# audio_spectrum.net
KiCad netlist of a schematic drawn in EAGLE
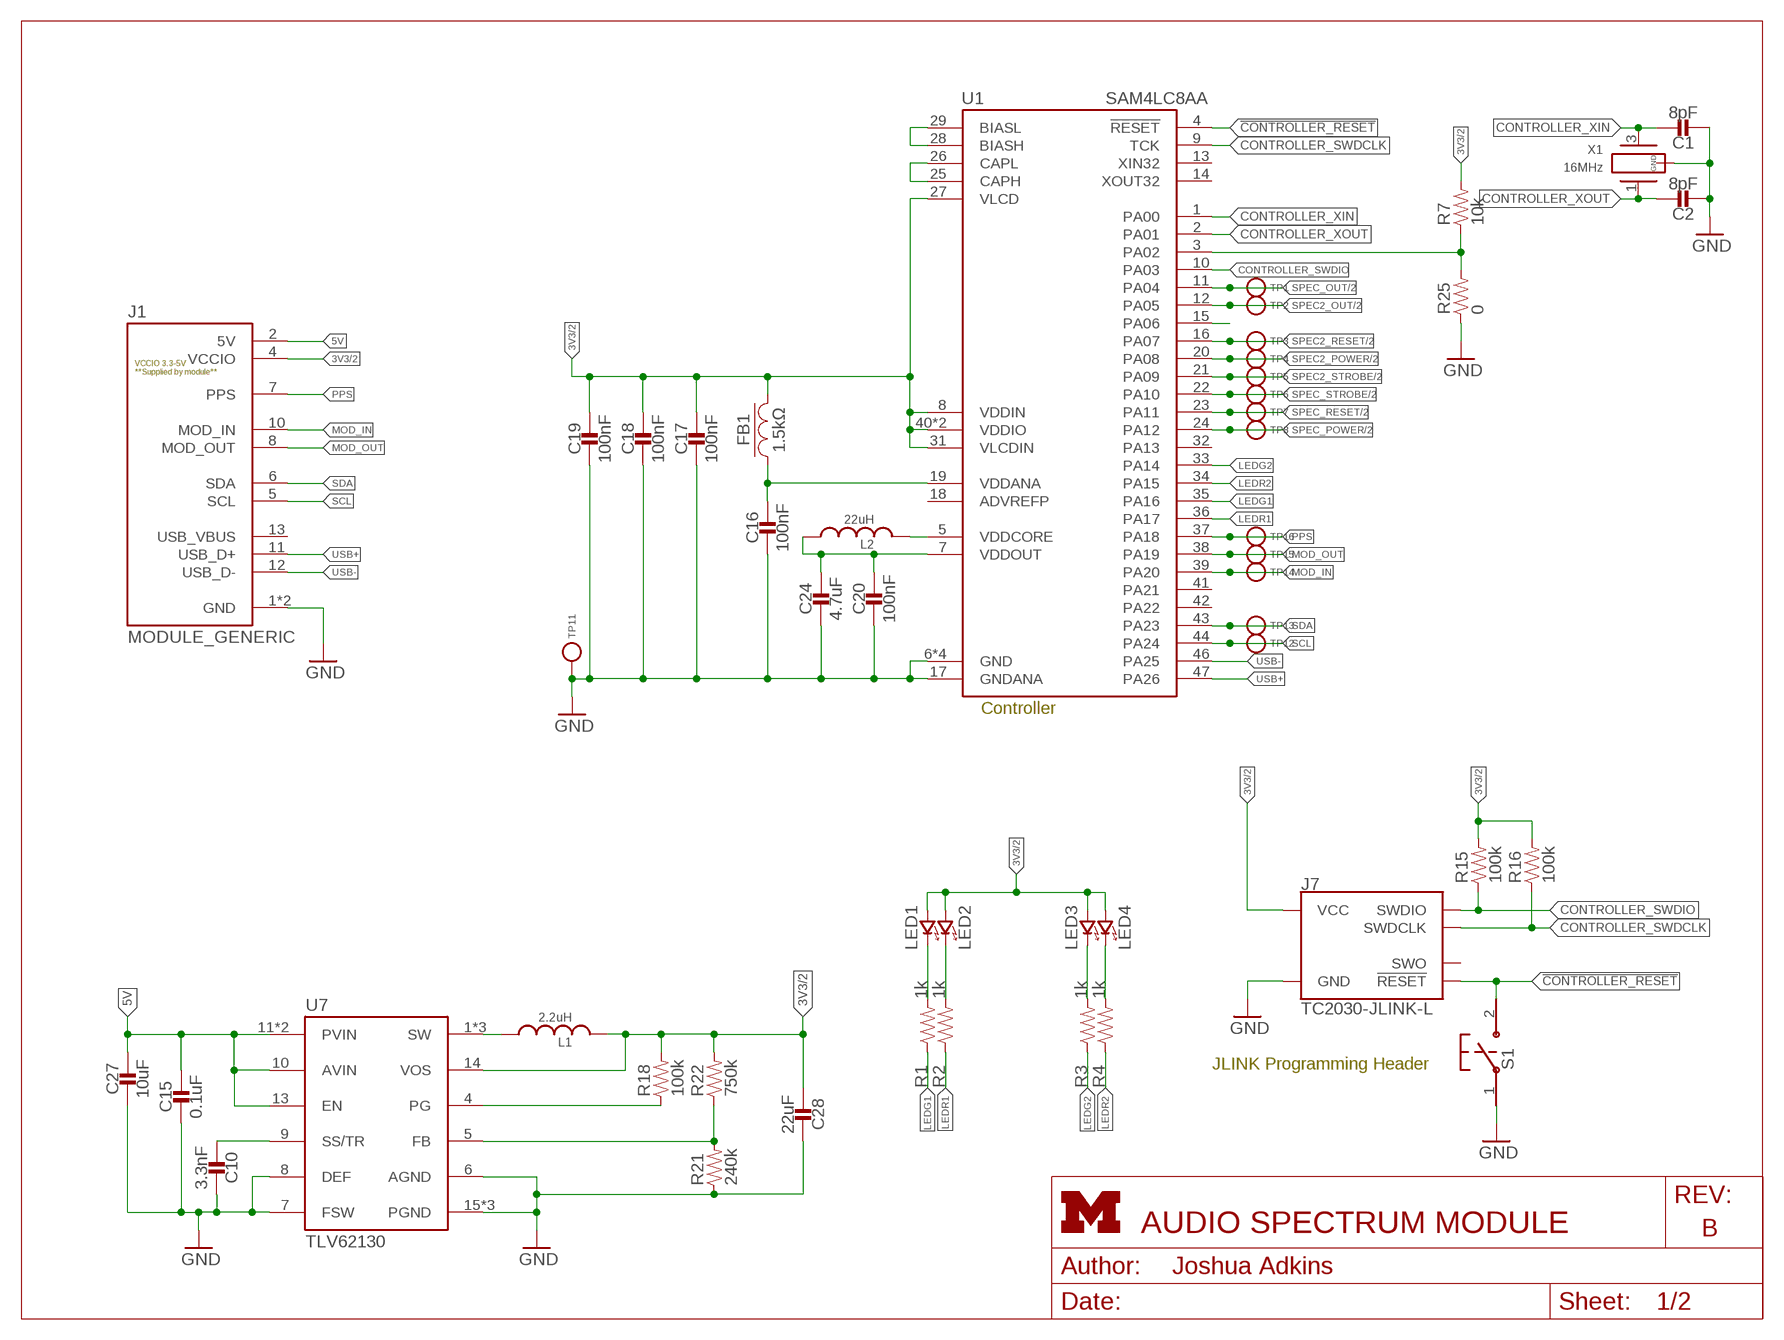
[diagram p0: schematic, sheet 1]
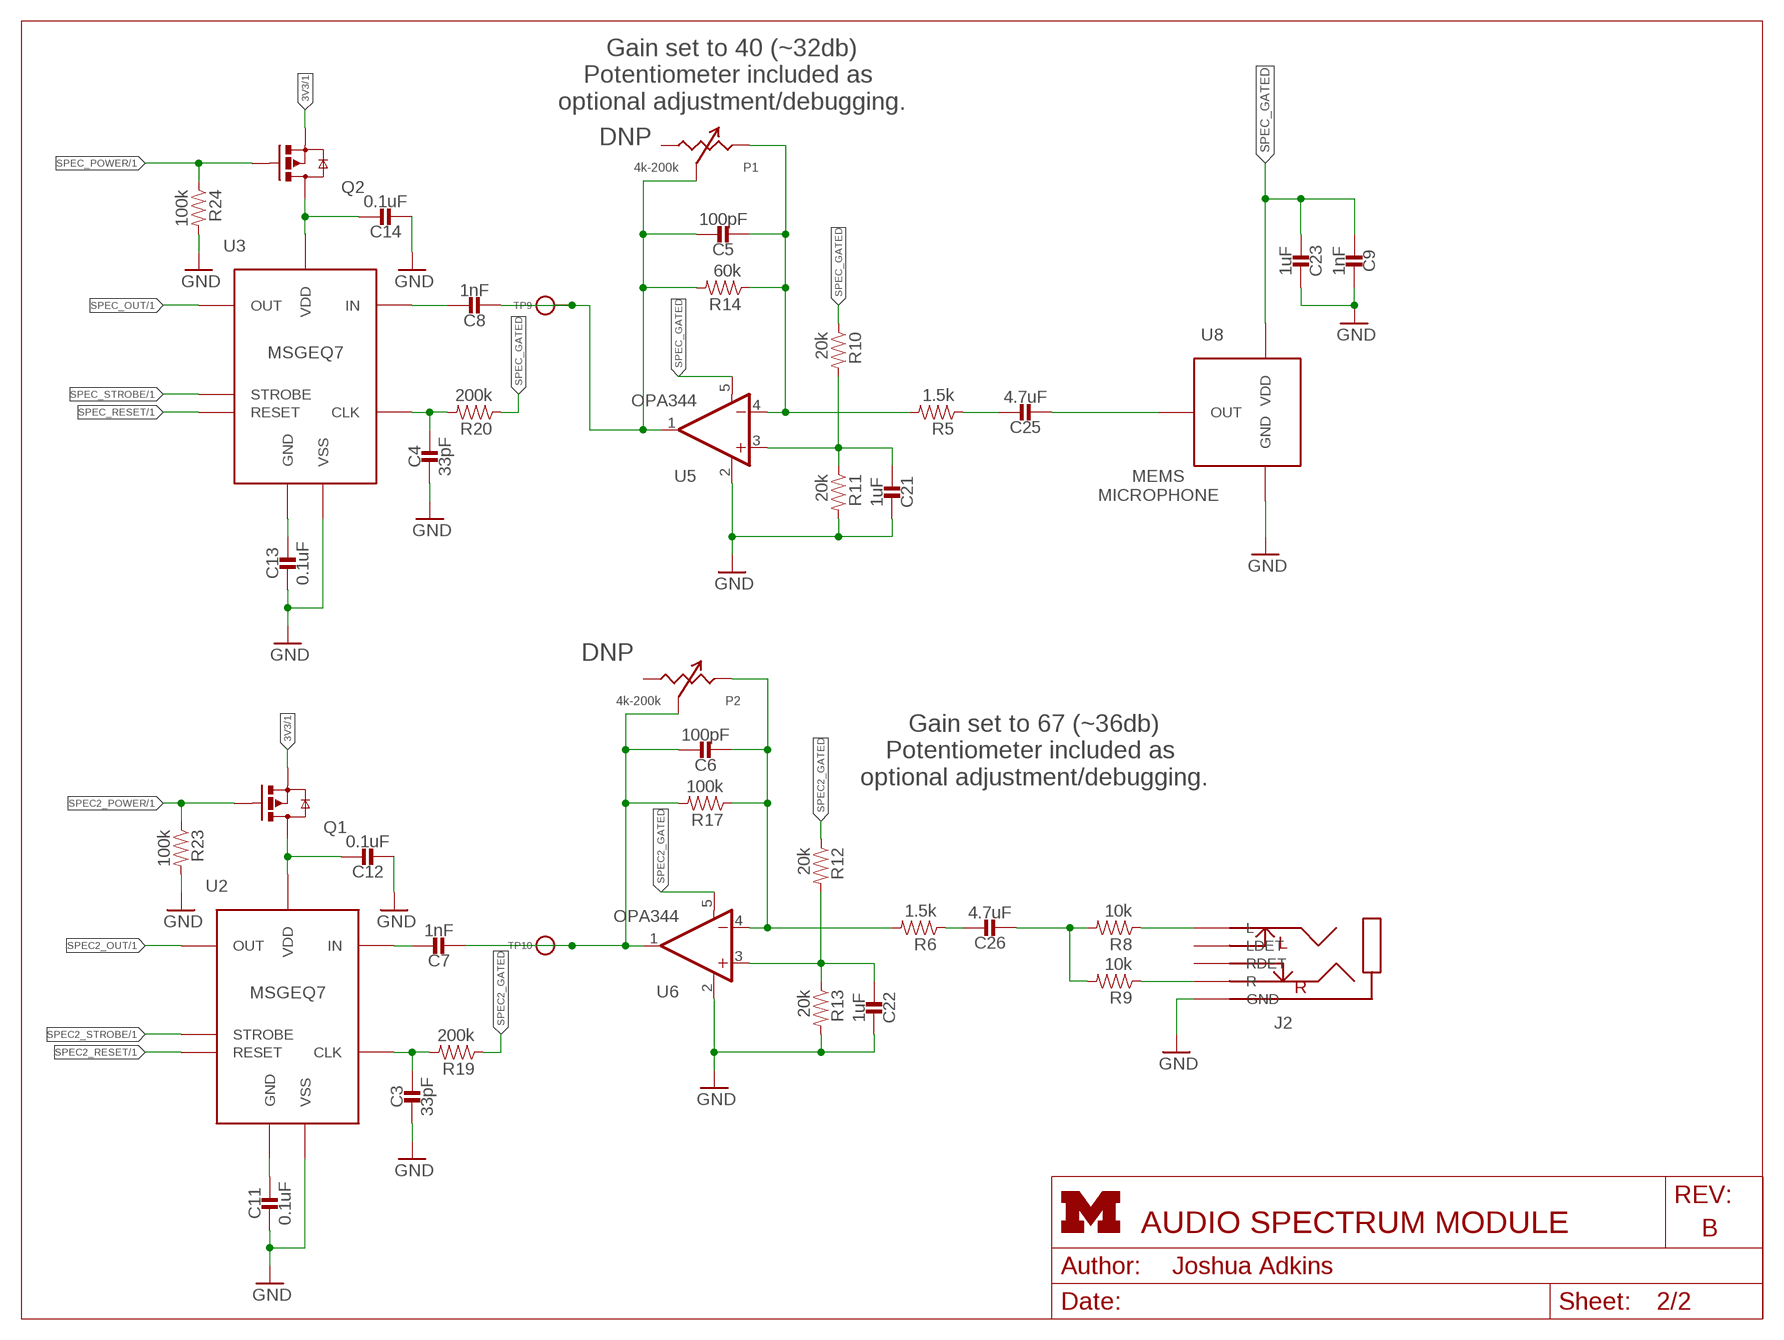
[diagram p1: schematic, sheet 2]

(export (version "E")
  (design (tool "Eeschema 10.0.6"))
  (components
    (comp (ref "C1")
      (value "8pF")
      (footprint "eagle-import:0603_CAP")
      (libsource (lib "eagle-import") (part "CAPACITOR0603_CAP"))
    )
    (comp (ref "C2")
      (value "8pF")
      (footprint "eagle-import:0603_CAP")
      (libsource (lib "eagle-import") (part "CAPACITOR0603_CAP"))
    )
    (comp (ref "C10")
      (value "3.3nF")
      (footprint "eagle-import:0603_CAP")
      (libsource (lib "eagle-import") (part "CAPACITOR0603_CAP"))
    )
    (comp (ref "C15")
      (value "0.1uF")
      (footprint "eagle-import:0603_CAP")
      (libsource (lib "eagle-import") (part "CAPACITOR0603_CAP"))
    )
    (comp (ref "C16")
      (value "100nF")
      (footprint "eagle-import:0603_CAP")
      (libsource (lib "eagle-import") (part "CAPACITOR0603_CAP"))
    )
    (comp (ref "C17")
      (value "100nF")
      (footprint "eagle-import:0603_CAP")
      (libsource (lib "eagle-import") (part "CAPACITOR0603_CAP"))
    )
    (comp (ref "C18")
      (value "100nF")
      (footprint "eagle-import:0603_CAP")
      (libsource (lib "eagle-import") (part "CAPACITOR0603_CAP"))
    )
    (comp (ref "C19")
      (value "100nF")
      (footprint "eagle-import:0603_CAP")
      (libsource (lib "eagle-import") (part "CAPACITOR0603_CAP"))
    )
    (comp (ref "C20")
      (value "100nF")
      (footprint "eagle-import:0402_CAP")
      (libsource (lib "eagle-import") (part "CAPACITOR0402_CAP"))
    )
    (comp (ref "C24")
      (value "4.7uF")
      (footprint "eagle-import:0402_CAP")
      (libsource (lib "eagle-import") (part "CAPACITOR0402_CAP"))
    )
    (comp (ref "C27")
      (value "10uF")
      (footprint "eagle-import:0603_CAP")
      (libsource (lib "eagle-import") (part "CAPACITOR0603_CAP"))
    )
    (comp (ref "C28")
      (value "22uF")
      (footprint "eagle-import:0603_CAP")
      (libsource (lib "eagle-import") (part "CAPACITOR0603_CAP"))
    )
    (comp (ref "FB1")
      (value "1.5kΩ")
      (footprint "eagle-import:0603_CAP")
      (libsource (lib "eagle-import") (part "FERRITE_BEAD0603"))
    )
    (comp (ref "J1")
      (value "MODULE_GENERIC")
      (footprint "eagle-import:MODULE_GENERIC")
      (libsource (lib "eagle-import") (part "MODULE_GENERIC"))
    )
    (comp (ref "J7")
      (value "TC2030-JLINK-L")
      (footprint "eagle-import:TC2030-IDC")
      (libsource (lib "eagle-import") (part "TC2030-JLINK-L"))
    )
    (comp (ref "L1")
      (value "2.2uH")
      (footprint "eagle-import:IHL-1212BZ-11")
      (libsource (lib "eagle-import") (part "INDUCTORIHL"))
    )
    (comp (ref "L2")
      (value "22uH")
      (footprint "eagle-import:1212")
      (libsource (lib "eagle-import") (part "LHQ3NP"))
    )
    (comp (ref "LED1")
      (value "LED0603")
      (footprint "eagle-import:LED-0603")
      (libsource (lib "eagle-import") (part "LED0603"))
    )
    (comp (ref "LED2")
      (value "LED0603")
      (footprint "eagle-import:LED-0603")
      (libsource (lib "eagle-import") (part "LED0603"))
    )
    (comp (ref "LED3")
      (value "LED0603")
      (footprint "eagle-import:LED-0603")
      (libsource (lib "eagle-import") (part "LED0603"))
    )
    (comp (ref "LED4")
      (value "LED0603")
      (footprint "eagle-import:LED-0603")
      (libsource (lib "eagle-import") (part "LED0603"))
    )
    (comp (ref "R1")
      (value "1k")
      (footprint "eagle-import:0603-RES")
      (libsource (lib "eagle-import") (part "RESISTOR0603_RES"))
    )
    (comp (ref "R2")
      (value "1k")
      (footprint "eagle-import:0603-RES")
      (libsource (lib "eagle-import") (part "RESISTOR0603_RES"))
    )
    (comp (ref "R3")
      (value "1k")
      (footprint "eagle-import:0603-RES")
      (libsource (lib "eagle-import") (part "RESISTOR0603_RES"))
    )
    (comp (ref "R4")
      (value "1k")
      (footprint "eagle-import:0603-RES")
      (libsource (lib "eagle-import") (part "RESISTOR0603_RES"))
    )
    (comp (ref "R7")
      (value "10k")
      (footprint "eagle-import:0603-RES")
      (libsource (lib "eagle-import") (part "RESISTOR0603_RES"))
    )
    (comp (ref "R15")
      (value "100k")
      (footprint "eagle-import:0603-RES")
      (libsource (lib "eagle-import") (part "RESISTOR0603_RES"))
    )
    (comp (ref "R16")
      (value "100k")
      (footprint "eagle-import:0603-RES")
      (libsource (lib "eagle-import") (part "RESISTOR0603_RES"))
    )
    (comp (ref "R18")
      (value "100k")
      (footprint "eagle-import:0603-RES")
      (libsource (lib "eagle-import") (part "RESISTOR0603_RES"))
    )
    (comp (ref "R21")
      (value "240k")
      (footprint "eagle-import:0603-RES")
      (libsource (lib "eagle-import") (part "RESISTOR0603_RES"))
    )
    (comp (ref "R22")
      (value "750k")
      (footprint "eagle-import:0603-RES")
      (libsource (lib "eagle-import") (part "RESISTOR0603_RES"))
    )
    (comp (ref "R25")
      (value "0")
      (footprint "eagle-import:0603-RES")
      (libsource (lib "eagle-import") (part "RESISTOR0603_RES"))
    )
    (comp (ref "S1")
      (value "B3U-1000P")
      (footprint "eagle-import:B3U-1000P")
      (libsource (lib "eagle-import") (part "B3U-1000P"))
    )
    (comp (ref "TP1")
      (value "TEST_POINT_0.040IN")
      (footprint "eagle-import:TESTPOINT_0.040IN")
      (libsource (lib "eagle-import") (part "TEST_POINT_0.040IN"))
    )
    (comp (ref "TP2")
      (value "TEST_POINT_0.040IN")
      (footprint "eagle-import:TESTPOINT_0.040IN")
      (libsource (lib "eagle-import") (part "TEST_POINT_0.040IN"))
    )
    (comp (ref "TP3")
      (value "TEST_POINT_0.040IN")
      (footprint "eagle-import:TESTPOINT_0.040IN")
      (libsource (lib "eagle-import") (part "TEST_POINT_0.040IN"))
    )
    (comp (ref "TP4")
      (value "TEST_POINT_0.040IN")
      (footprint "eagle-import:TESTPOINT_0.040IN")
      (libsource (lib "eagle-import") (part "TEST_POINT_0.040IN"))
    )
    (comp (ref "TP5")
      (value "TEST_POINT_0.040IN")
      (footprint "eagle-import:TESTPOINT_0.040IN")
      (libsource (lib "eagle-import") (part "TEST_POINT_0.040IN"))
    )
    (comp (ref "TP6")
      (value "TEST_POINT_0.040IN")
      (footprint "eagle-import:TESTPOINT_0.040IN")
      (libsource (lib "eagle-import") (part "TEST_POINT_0.040IN"))
    )
    (comp (ref "TP7")
      (value "TEST_POINT_0.040IN")
      (footprint "eagle-import:TESTPOINT_0.040IN")
      (libsource (lib "eagle-import") (part "TEST_POINT_0.040IN"))
    )
    (comp (ref "TP8")
      (value "TEST_POINT_0.040IN")
      (footprint "eagle-import:TESTPOINT_0.040IN")
      (libsource (lib "eagle-import") (part "TEST_POINT_0.040IN"))
    )
    (comp (ref "TP11")
      (value "TEST_POINT_0.040IN")
      (footprint "eagle-import:TESTPOINT_0.040IN")
      (libsource (lib "eagle-import") (part "TEST_POINT_0.040IN"))
    )
    (comp (ref "TP12")
      (value "TEST_POINT_0.040IN")
      (footprint "eagle-import:TESTPOINT_0.040IN")
      (libsource (lib "eagle-import") (part "TEST_POINT_0.040IN"))
    )
    (comp (ref "TP13")
      (value "TEST_POINT_0.040IN")
      (footprint "eagle-import:TESTPOINT_0.040IN")
      (libsource (lib "eagle-import") (part "TEST_POINT_0.040IN"))
    )
    (comp (ref "TP14")
      (value "TEST_POINT_0.040IN")
      (footprint "eagle-import:TESTPOINT_0.040IN")
      (libsource (lib "eagle-import") (part "TEST_POINT_0.040IN"))
    )
    (comp (ref "TP15")
      (value "TEST_POINT_0.040IN")
      (footprint "eagle-import:TESTPOINT_0.040IN")
      (libsource (lib "eagle-import") (part "TEST_POINT_0.040IN"))
    )
    (comp (ref "TP16")
      (value "TEST_POINT_0.040IN")
      (footprint "eagle-import:TESTPOINT_0.040IN")
      (libsource (lib "eagle-import") (part "TEST_POINT_0.040IN"))
    )
    (comp (ref "U1")
      (value "SAM4LC8AA")
      (footprint "eagle-import:QFN-48-7MM")
      (libsource (lib "eagle-import") (part "SAM4LC8AA"))
    )
    (comp (ref "U7")
      (value "TLV62130")
      (footprint "eagle-import:TQFN-16_3MM")
      (libsource (lib "eagle-import") (part "TLV62130"))
    )
    (comp (ref "X1")
      (value "16MHz")
      (footprint "eagle-import:FHXXX")
      (libsource (lib "eagle-import") (part "FH1600015"))
    )
    (comp (ref "C3")
      (value "33pF")
      (footprint "eagle-import:0603_CAP")
      (libsource (lib "eagle-import") (part "CAPACITOR0603_CAP"))
    )
    (comp (ref "C4")
      (value "33pF")
      (footprint "eagle-import:0603_CAP")
      (libsource (lib "eagle-import") (part "CAPACITOR0603_CAP"))
    )
    (comp (ref "C5")
      (value "100pF")
      (footprint "eagle-import:0603_CAP")
      (libsource (lib "eagle-import") (part "CAPACITOR0603_CAP"))
    )
    (comp (ref "C6")
      (value "100pF")
      (footprint "eagle-import:0603_CAP")
      (libsource (lib "eagle-import") (part "CAPACITOR0603_CAP"))
    )
    (comp (ref "C7")
      (value "1nF")
      (footprint "eagle-import:0603_CAP")
      (libsource (lib "eagle-import") (part "CAPACITOR0603_CAP"))
    )
    (comp (ref "C8")
      (value "1nF")
      (footprint "eagle-import:0603_CAP")
      (libsource (lib "eagle-import") (part "CAPACITOR0603_CAP"))
    )
    (comp (ref "C9")
      (value "1nF")
      (footprint "eagle-import:0603_CAP")
      (libsource (lib "eagle-import") (part "CAPACITOR0603_CAP"))
    )
    (comp (ref "C11")
      (value "0.1uF")
      (footprint "eagle-import:0603_CAP")
      (libsource (lib "eagle-import") (part "CAPACITOR0603_CAP"))
    )
    (comp (ref "C12")
      (value "0.1uF")
      (footprint "eagle-import:0603_CAP")
      (libsource (lib "eagle-import") (part "CAPACITOR0603_CAP"))
    )
    (comp (ref "C13")
      (value "0.1uF")
      (footprint "eagle-import:0603_CAP")
      (libsource (lib "eagle-import") (part "CAPACITOR0603_CAP"))
    )
    (comp (ref "C14")
      (value "0.1uF")
      (footprint "eagle-import:0603_CAP")
      (libsource (lib "eagle-import") (part "CAPACITOR0603_CAP"))
    )
    (comp (ref "C21")
      (value "1uF")
      (footprint "eagle-import:0603_CAP")
      (libsource (lib "eagle-import") (part "CAPACITOR0603_CAP"))
    )
    (comp (ref "C22")
      (value "1uF")
      (footprint "eagle-import:0603_CAP")
      (libsource (lib "eagle-import") (part "CAPACITOR0603_CAP"))
    )
    (comp (ref "C23")
      (value "1uF")
      (footprint "eagle-import:0603_CAP")
      (libsource (lib "eagle-import") (part "CAPACITOR0603_CAP"))
    )
    (comp (ref "C25")
      (value "4.7uF")
      (footprint "eagle-import:0603_CAP")
      (libsource (lib "eagle-import") (part "CAPACITOR0603_CAP"))
    )
    (comp (ref "C26")
      (value "4.7uF")
      (footprint "eagle-import:0603_CAP")
      (libsource (lib "eagle-import") (part "CAPACITOR0603_CAP"))
    )
    (comp (ref "J2")
      (value "AUDIO-JACK-VERTICAL")
      (footprint "eagle-import:AUDIO-JACK-VERTICAL")
      (libsource (lib "eagle-import") (part "AUDIO-JACK-VERTICAL"))
    )
    (comp (ref "P1")
      (value "4k-200k")
      (footprint "eagle-import:TC33X-2")
      (libsource (lib "eagle-import") (part "POTTC33X"))
    )
    (comp (ref "P2")
      (value "4k-200k")
      (footprint "eagle-import:TC33X-2")
      (libsource (lib "eagle-import") (part "POTTC33X"))
    )
    (comp (ref "Q1")
      (value "NX3008PBK")
      (footprint "eagle-import:SOT23-3")
      (libsource (lib "eagle-import") (part "NX3008PBK"))
    )
    (comp (ref "Q2")
      (value "NX3008PBK")
      (footprint "eagle-import:SOT23-3")
      (libsource (lib "eagle-import") (part "NX3008PBK"))
    )
    (comp (ref "R5")
      (value "1.5k")
      (footprint "eagle-import:0603-RES")
      (libsource (lib "eagle-import") (part "RESISTOR0603_RES"))
    )
    (comp (ref "R6")
      (value "1.5k")
      (footprint "eagle-import:0603-RES")
      (libsource (lib "eagle-import") (part "RESISTOR0603_RES"))
    )
    (comp (ref "R8")
      (value "10k")
      (footprint "eagle-import:0603-RES")
      (libsource (lib "eagle-import") (part "RESISTOR0603_RES"))
    )
    (comp (ref "R9")
      (value "10k")
      (footprint "eagle-import:0603-RES")
      (libsource (lib "eagle-import") (part "RESISTOR0603_RES"))
    )
    (comp (ref "R10")
      (value "20k")
      (footprint "eagle-import:0603-RES")
      (libsource (lib "eagle-import") (part "RESISTOR0603_RES"))
    )
    (comp (ref "R11")
      (value "20k")
      (footprint "eagle-import:0603-RES")
      (libsource (lib "eagle-import") (part "RESISTOR0603_RES"))
    )
    (comp (ref "R12")
      (value "20k")
      (footprint "eagle-import:0603-RES")
      (libsource (lib "eagle-import") (part "RESISTOR0603_RES"))
    )
    (comp (ref "R13")
      (value "20k")
      (footprint "eagle-import:0603-RES")
      (libsource (lib "eagle-import") (part "RESISTOR0603_RES"))
    )
    (comp (ref "R14")
      (value "60k")
      (footprint "eagle-import:0603-RES")
      (libsource (lib "eagle-import") (part "RESISTOR0603_RES"))
    )
    (comp (ref "R17")
      (value "100k")
      (footprint "eagle-import:0603-RES")
      (libsource (lib "eagle-import") (part "RESISTOR0603_RES"))
    )
    (comp (ref "R19")
      (value "200k")
      (footprint "eagle-import:0603-RES")
      (libsource (lib "eagle-import") (part "RESISTOR0603_RES"))
    )
    (comp (ref "R20")
      (value "200k")
      (footprint "eagle-import:0603-RES")
      (libsource (lib "eagle-import") (part "RESISTOR0603_RES"))
    )
    (comp (ref "R23")
      (value "100k")
      (footprint "eagle-import:0603-RES")
      (libsource (lib "eagle-import") (part "RESISTOR0603_RES"))
    )
    (comp (ref "R24")
      (value "100k")
      (footprint "eagle-import:0603-RES")
      (libsource (lib "eagle-import") (part "RESISTOR0603_RES"))
    )
    (comp (ref "TP9")
      (value "TEST_POINT_0.040IN")
      (footprint "eagle-import:TESTPOINT_0.040IN")
      (libsource (lib "eagle-import") (part "TEST_POINT_0.040IN"))
    )
    (comp (ref "TP10")
      (value "TEST_POINT_0.040IN")
      (footprint "eagle-import:TESTPOINT_0.040IN")
      (libsource (lib "eagle-import") (part "TEST_POINT_0.040IN"))
    )
    (comp (ref "U2")
      (value "MSGEQ7")
      (footprint "eagle-import:DIP-8")
      (libsource (lib "eagle-import") (part "MSGEQ7"))
    )
    (comp (ref "U3")
      (value "MSGEQ7")
      (footprint "eagle-import:DIP-8")
      (libsource (lib "eagle-import") (part "MSGEQ7"))
    )
    (comp (ref "U5")
      (value "OPA344")
      (footprint "eagle-import:SOT23-5")
      (libsource (lib "eagle-import") (part "OPA344"))
    )
    (comp (ref "U6")
      (value "OPA344")
      (footprint "eagle-import:SOT23-5")
      (libsource (lib "eagle-import") (part "OPA344"))
    )
    (comp (ref "U8")
      (value "MP23AB02B")
      (footprint "eagle-import:MP23AB02B")
      (libsource (lib "eagle-import") (part "MP23AB02B"))
    )
  )
  (nets
    (net (code "1") (name "3V3") (class "Default")
      (node (ref "C17") (pin "1") (pinfunction "1_1") (pintype "bidirectional"))
      (node (ref "C18") (pin "1") (pinfunction "1_1") (pintype "bidirectional"))
      (node (ref "C19") (pin "1") (pinfunction "1_1") (pintype "bidirectional"))
      (node (ref "C28") (pin "2") (pinfunction "2_2") (pintype "bidirectional"))
      (node (ref "FB1") (pin "2") (pinfunction "P$2_2") (pintype "bidirectional"))
      (node (ref "J1") (pin "4") (pinfunction "VCCIO_4") (pintype "bidirectional"))
      (node (ref "J7") (pin "1") (pinfunction "VCC_1") (pintype "bidirectional"))
      (node (ref "L1") (pin "P$2") (pinfunction "2_P$2") (pintype "bidirectional"))
      (node (ref "LED1") (pin "A") (pinfunction "ANODE_A") (pintype "bidirectional"))
      (node (ref "LED2") (pin "A") (pinfunction "ANODE_A") (pintype "bidirectional"))
      (node (ref "LED3") (pin "A") (pinfunction "ANODE_A") (pintype "bidirectional"))
      (node (ref "LED4") (pin "A") (pinfunction "ANODE_A") (pintype "bidirectional"))
      (node (ref "Q1") (pin "2") (pinfunction "S_2") (pintype "passive"))
      (node (ref "Q2") (pin "2") (pinfunction "S_2") (pintype "passive"))
      (node (ref "R15") (pin "2") (pinfunction "2_2") (pintype "passive"))
      (node (ref "R16") (pin "2") (pinfunction "2_2") (pintype "passive"))
      (node (ref "R18") (pin "2") (pinfunction "2_2") (pintype "passive"))
      (node (ref "R22") (pin "2") (pinfunction "2_2") (pintype "passive"))
      (node (ref "R7") (pin "2") (pinfunction "2_2") (pintype "passive"))
      (node (ref "U1") (pin "27") (pinfunction "VLCD_27") (pintype "bidirectional"))
      (node (ref "U1") (pin "31") (pinfunction "VLCDIN_31") (pintype "power_in"))
      (node (ref "U1") (pin "40") (pinfunction "VDDIO_40") (pintype "power_in"))
      (node (ref "U1") (pin "45") (pinfunction "VDDIO_45") (pintype "power_in"))
      (node (ref "U1") (pin "8") (pinfunction "VDDIN_8") (pintype "power_in"))
      (node (ref "U7") (pin "14") (pinfunction "VOS_14") (pintype "bidirectional"))
    )
    (net (code "2") (name "5V") (class "Default")
      (node (ref "C15") (pin "1") (pinfunction "1_1") (pintype "bidirectional"))
      (node (ref "C27") (pin "1") (pinfunction "1_1") (pintype "bidirectional"))
      (node (ref "J1") (pin "2") (pinfunction "5V_2") (pintype "bidirectional"))
      (node (ref "U7") (pin "10") (pinfunction "AVIN_10") (pintype "bidirectional"))
      (node (ref "U7") (pin "11") (pinfunction "PVIN_11") (pintype "bidirectional"))
      (node (ref "U7") (pin "12") (pinfunction "PVIN_12") (pintype "bidirectional"))
      (node (ref "U7") (pin "13") (pinfunction "EN_13") (pintype "bidirectional"))
    )
    (net (code "3") (name "CONTROLLER_SWDCLK") (class "Default")
      (node (ref "J7") (pin "4") (pinfunction "SWDCLK_4") (pintype "bidirectional"))
      (node (ref "R16") (pin "1") (pinfunction "1_1") (pintype "passive"))
      (node (ref "U1") (pin "9") (pinfunction "TCK_9") (pintype "bidirectional"))
    )
    (net (code "4") (name "CONTROLLER_SWDIO") (class "Default")
      (node (ref "J7") (pin "2") (pinfunction "SWDIO_2") (pintype "bidirectional"))
      (node (ref "R15") (pin "1") (pinfunction "1_1") (pintype "passive"))
      (node (ref "U1") (pin "10") (pinfunction "PA03_10") (pintype "bidirectional"))
    )
    (net (code "5") (name "CONTROLLER_XIN") (class "Default")
      (node (ref "C1") (pin "1") (pinfunction "1_1") (pintype "bidirectional"))
      (node (ref "U1") (pin "1") (pinfunction "PA00_1") (pintype "bidirectional"))
      (node (ref "X1") (pin "3") (pinfunction "2_3") (pintype "bidirectional"))
    )
    (net (code "6") (name "CONTROLLER_XOUT") (class "Default")
      (node (ref "C2") (pin "1") (pinfunction "1_1") (pintype "bidirectional"))
      (node (ref "U1") (pin "2") (pinfunction "PA01_2") (pintype "bidirectional"))
      (node (ref "X1") (pin "1") (pinfunction "1_1") (pintype "bidirectional"))
    )
    (net (code "7") (name "GND") (class "Default")
      (node (ref "C1") (pin "2") (pinfunction "2_2") (pintype "bidirectional"))
      (node (ref "C10") (pin "1") (pinfunction "1_1") (pintype "bidirectional"))
      (node (ref "C11") (pin "2") (pinfunction "2_2") (pintype "bidirectional"))
      (node (ref "C12") (pin "2") (pinfunction "2_2") (pintype "bidirectional"))
      (node (ref "C13") (pin "2") (pinfunction "2_2") (pintype "bidirectional"))
      (node (ref "C14") (pin "2") (pinfunction "2_2") (pintype "bidirectional"))
      (node (ref "C15") (pin "2") (pinfunction "2_2") (pintype "bidirectional"))
      (node (ref "C16") (pin "2") (pinfunction "2_2") (pintype "bidirectional"))
      (node (ref "C17") (pin "2") (pinfunction "2_2") (pintype "bidirectional"))
      (node (ref "C18") (pin "2") (pinfunction "2_2") (pintype "bidirectional"))
      (node (ref "C19") (pin "2") (pinfunction "2_2") (pintype "bidirectional"))
      (node (ref "C2") (pin "2") (pinfunction "2_2") (pintype "bidirectional"))
      (node (ref "C20") (pin "2") (pinfunction "2_2") (pintype "bidirectional"))
      (node (ref "C21") (pin "1") (pinfunction "1_1") (pintype "bidirectional"))
      (node (ref "C22") (pin "1") (pinfunction "1_1") (pintype "bidirectional"))
      (node (ref "C23") (pin "1") (pinfunction "1_1") (pintype "bidirectional"))
      (node (ref "C24") (pin "2") (pinfunction "2_2") (pintype "bidirectional"))
      (node (ref "C27") (pin "2") (pinfunction "2_2") (pintype "bidirectional"))
      (node (ref "C28") (pin "1") (pinfunction "1_1") (pintype "bidirectional"))
      (node (ref "C3") (pin "2") (pinfunction "2_2") (pintype "bidirectional"))
      (node (ref "C4") (pin "2") (pinfunction "2_2") (pintype "bidirectional"))
      (node (ref "C9") (pin "1") (pinfunction "1_1") (pintype "bidirectional"))
      (node (ref "J1") (pin "1") (pinfunction "GND_1") (pintype "bidirectional"))
      (node (ref "J1") (pin "14") (pinfunction "GND_14") (pintype "bidirectional"))
      (node (ref "J2") (pin "5") (pinfunction "GND_5") (pintype "bidirectional"))
      (node (ref "J7") (pin "5") (pinfunction "GND_5") (pintype "bidirectional"))
      (node (ref "R11") (pin "2") (pinfunction "2_2") (pintype "passive"))
      (node (ref "R13") (pin "2") (pinfunction "2_2") (pintype "passive"))
      (node (ref "R21") (pin "1") (pinfunction "1_1") (pintype "passive"))
      (node (ref "R23") (pin "2") (pinfunction "2_2") (pintype "passive"))
      (node (ref "R24") (pin "2") (pinfunction "2_2") (pintype "passive"))
      (node (ref "R25") (pin "1") (pinfunction "1_1") (pintype "passive"))
      (node (ref "S1") (pin "1") (pinfunction "P$1_1") (pintype "passive"))
      (node (ref "TP11") (pin "TESTPOINT") (pinfunction "TESTPOINT_TESTPOINT") (pintype "bidirectional"))
      (node (ref "U1") (pin "17") (pinfunction "GNDANA_17") (pintype "power_in"))
      (node (ref "U1") (pin "30") (pinfunction "GND_30") (pintype "power_in"))
      (node (ref "U1") (pin "48") (pinfunction "GND_48") (pintype "power_in"))
      (node (ref "U1") (pin "6") (pinfunction "GND_6") (pintype "power_in"))
      (node (ref "U1") (pin "THERMAL") (pinfunction "GND_THERMAL") (pintype "power_in"))
      (node (ref "U2") (pin "2") (pinfunction "VSS_2") (pintype "bidirectional"))
      (node (ref "U3") (pin "2") (pinfunction "VSS_2") (pintype "bidirectional"))
      (node (ref "U5") (pin "2") (pinfunction "V-_2") (pintype "power_in"))
      (node (ref "U6") (pin "2") (pinfunction "V-_2") (pintype "power_in"))
      (node (ref "U7") (pin "15") (pinfunction "PGND_15") (pintype "bidirectional"))
      (node (ref "U7") (pin "16") (pinfunction "PGND_16") (pintype "bidirectional"))
      (node (ref "U7") (pin "6") (pinfunction "AGND_6") (pintype "bidirectional"))
      (node (ref "U7") (pin "7") (pinfunction "FSW_7") (pintype "bidirectional"))
      (node (ref "U7") (pin "8") (pinfunction "DEF_8") (pintype "bidirectional"))
      (node (ref "U7") (pin "GND") (pinfunction "PGND_GND") (pintype "bidirectional"))
      (node (ref "U8") (pin "3") (pinfunction "GND_3") (pintype "bidirectional"))
      (node (ref "X1") (pin "2") (pinfunction "GND_2") (pintype "bidirectional"))
      (node (ref "X1") (pin "4") (pinfunction "GND_4") (pintype "bidirectional"))
    )
    (net (code "8") (name "LEDG1") (class "Default")
      (node (ref "R1") (pin "1") (pinfunction "1_1") (pintype "passive"))
      (node (ref "U1") (pin "35") (pinfunction "PA16_35") (pintype "bidirectional"))
    )
    (net (code "9") (name "LEDG2") (class "Default")
      (node (ref "R3") (pin "1") (pinfunction "1_1") (pintype "passive"))
      (node (ref "U1") (pin "33") (pinfunction "PA14_33") (pintype "bidirectional"))
    )
    (net (code "10") (name "LEDR1") (class "Default")
      (node (ref "R2") (pin "1") (pinfunction "1_1") (pintype "passive"))
      (node (ref "U1") (pin "36") (pinfunction "PA17_36") (pintype "bidirectional"))
    )
    (net (code "11") (name "LEDR2") (class "Default")
      (node (ref "R4") (pin "1") (pinfunction "1_1") (pintype "passive"))
      (node (ref "U1") (pin "34") (pinfunction "PA15_34") (pintype "bidirectional"))
    )
    (net (code "12") (name "MOD_IN") (class "Default")
      (node (ref "J1") (pin "10") (pinfunction "MOD_IN_10") (pintype "bidirectional"))
      (node (ref "TP14") (pin "TESTPOINT") (pinfunction "TESTPOINT_TESTPOINT") (pintype "bidirectional"))
      (node (ref "U1") (pin "39") (pinfunction "PA20_39") (pintype "bidirectional"))
    )
    (net (code "13") (name "MOD_OUT") (class "Default")
      (node (ref "J1") (pin "8") (pinfunction "MOD_OUT_8") (pintype "bidirectional"))
      (node (ref "TP15") (pin "TESTPOINT") (pinfunction "TESTPOINT_TESTPOINT") (pintype "bidirectional"))
      (node (ref "U1") (pin "38") (pinfunction "PA19_38") (pintype "bidirectional"))
    )
    (net (code "14") (name "Net-(C25-Pad1)") (class "Default")
      (node (ref "C25") (pin "1") (pinfunction "1_1") (pintype "bidirectional"))
      (node (ref "R5") (pin "1") (pinfunction "1_1") (pintype "passive"))
    )
    (net (code "15") (name "Net-(C26-Pad1)") (class "Default")
      (node (ref "C26") (pin "1") (pinfunction "1_1") (pintype "bidirectional"))
      (node (ref "R6") (pin "1") (pinfunction "1_1") (pintype "passive"))
    )
    (net (code "16") (name "Net-(C26-Pad2)") (class "Default")
      (node (ref "C26") (pin "2") (pinfunction "2_2") (pintype "bidirectional"))
      (node (ref "R8") (pin "2") (pinfunction "2_2") (pintype "passive"))
      (node (ref "R9") (pin "2") (pinfunction "2_2") (pintype "passive"))
    )
    (net (code "17") (name "Net-(FB1-P$1)") (class "Default")
      (node (ref "C16") (pin "1") (pinfunction "1_1") (pintype "bidirectional"))
      (node (ref "FB1") (pin "1") (pinfunction "P$1_1") (pintype "bidirectional"))
      (node (ref "U1") (pin "19") (pinfunction "VDDANA_19") (pintype "power_in"))
    )
    (net (code "18") (name "Net-(J2-L)") (class "Default")
      (node (ref "J2") (pin "4") (pinfunction "L_4") (pintype "bidirectional"))
      (node (ref "R8") (pin "1") (pinfunction "1_1") (pintype "passive"))
    )
    (net (code "19") (name "Net-(J2-R)") (class "Default")
      (node (ref "J2") (pin "1") (pinfunction "R_1") (pintype "bidirectional"))
      (node (ref "R9") (pin "1") (pinfunction "1_1") (pintype "passive"))
    )
    (net (code "20") (name "Net-(L1-1)") (class "Default")
      (node (ref "L1") (pin "P$1") (pinfunction "1_P$1") (pintype "bidirectional"))
      (node (ref "U7") (pin "1") (pinfunction "SW_1") (pintype "bidirectional"))
      (node (ref "U7") (pin "2") (pinfunction "SW_2") (pintype "bidirectional"))
      (node (ref "U7") (pin "3") (pinfunction "SW_3") (pintype "bidirectional"))
    )
    (net (code "21") (name "Net-(L2-1)") (class "Default")
      (node (ref "C20") (pin "1") (pinfunction "1_1") (pintype "bidirectional"))
      (node (ref "C24") (pin "1") (pinfunction "1_1") (pintype "bidirectional"))
      (node (ref "L2") (pin "P$1") (pinfunction "1_P$1") (pintype "bidirectional"))
      (node (ref "U1") (pin "7") (pinfunction "VDDOUT_7") (pintype "power_in"))
    )
    (net (code "22") (name "Net-(L2-2)") (class "Default")
      (node (ref "L2") (pin "P$2") (pinfunction "2_P$2") (pintype "bidirectional"))
      (node (ref "U1") (pin "5") (pinfunction "VDDCORE_5") (pintype "power_in"))
    )
    (net (code "23") (name "Net-(LED1-CATHODE)") (class "Default")
      (node (ref "LED1") (pin "C") (pinfunction "CATHODE_C") (pintype "bidirectional"))
      (node (ref "R1") (pin "2") (pinfunction "2_2") (pintype "passive"))
    )
    (net (code "24") (name "Net-(LED2-CATHODE)") (class "Default")
      (node (ref "LED2") (pin "C") (pinfunction "CATHODE_C") (pintype "bidirectional"))
      (node (ref "R2") (pin "2") (pinfunction "2_2") (pintype "passive"))
    )
    (net (code "25") (name "Net-(LED3-CATHODE)") (class "Default")
      (node (ref "LED3") (pin "C") (pinfunction "CATHODE_C") (pintype "bidirectional"))
      (node (ref "R3") (pin "2") (pinfunction "2_2") (pintype "passive"))
    )
    (net (code "26") (name "Net-(LED4-CATHODE)") (class "Default")
      (node (ref "LED4") (pin "C") (pinfunction "CATHODE_C") (pintype "bidirectional"))
      (node (ref "R4") (pin "2") (pinfunction "2_2") (pintype "passive"))
    )
    (net (code "27") (name "Net-(P1-CW)") (class "Default")
      (node (ref "C5") (pin "2") (pinfunction "2_2") (pintype "bidirectional"))
      (node (ref "P1") (pin "2") (pinfunction "CW_2") (pintype "bidirectional"))
      (node (ref "R14") (pin "1") (pinfunction "1_1") (pintype "passive"))
      (node (ref "R5") (pin "2") (pinfunction "2_2") (pintype "passive"))
      (node (ref "U5") (pin "4") (pinfunction "-IN_4") (pintype "input"))
    )
    (net (code "28") (name "Net-(P1-W)") (class "Default")
      (node (ref "C5") (pin "1") (pinfunction "1_1") (pintype "bidirectional"))
      (node (ref "C8") (pin "2") (pinfunction "2_2") (pintype "bidirectional"))
      (node (ref "P1") (pin "3") (pinfunction "W_3") (pintype "bidirectional"))
      (node (ref "R14") (pin "2") (pinfunction "2_2") (pintype "passive"))
      (node (ref "TP9") (pin "TESTPOINT") (pinfunction "TESTPOINT_TESTPOINT") (pintype "bidirectional"))
      (node (ref "U5") (pin "1") (pinfunction "OUT_1") (pintype "output"))
    )
    (net (code "29") (name "Net-(P2-CW)") (class "Default")
      (node (ref "C6") (pin "2") (pinfunction "2_2") (pintype "bidirectional"))
      (node (ref "P2") (pin "2") (pinfunction "CW_2") (pintype "bidirectional"))
      (node (ref "R17") (pin "1") (pinfunction "1_1") (pintype "passive"))
      (node (ref "R6") (pin "2") (pinfunction "2_2") (pintype "passive"))
      (node (ref "U6") (pin "4") (pinfunction "-IN_4") (pintype "input"))
    )
    (net (code "30") (name "Net-(P2-W)") (class "Default")
      (node (ref "C6") (pin "1") (pinfunction "1_1") (pintype "bidirectional"))
      (node (ref "C7") (pin "2") (pinfunction "2_2") (pintype "bidirectional"))
      (node (ref "P2") (pin "3") (pinfunction "W_3") (pintype "bidirectional"))
      (node (ref "R17") (pin "2") (pinfunction "2_2") (pintype "passive"))
      (node (ref "TP10") (pin "TESTPOINT") (pinfunction "TESTPOINT_TESTPOINT") (pintype "bidirectional"))
      (node (ref "U6") (pin "1") (pinfunction "OUT_1") (pintype "output"))
    )
    (net (code "31") (name "Net-(U1-BIASH)") (class "Default")
      (node (ref "U1") (pin "28") (pinfunction "BIASH_28") (pintype "bidirectional"))
      (node (ref "U1") (pin "29") (pinfunction "BIASL_29") (pintype "bidirectional"))
    )
    (net (code "32") (name "Net-(U1-CAPH)") (class "Default")
      (node (ref "U1") (pin "25") (pinfunction "CAPH_25") (pintype "bidirectional"))
      (node (ref "U1") (pin "26") (pinfunction "CAPL_26") (pintype "bidirectional"))
    )
    (net (code "33") (name "Net-(U1-PA02)") (class "Default")
      (node (ref "R25") (pin "2") (pinfunction "2_2") (pintype "passive"))
      (node (ref "R7") (pin "1") (pinfunction "1_1") (pintype "passive"))
      (node (ref "U1") (pin "3") (pinfunction "PA02_3") (pintype "bidirectional"))
    )
    (net (code "34") (name "Net-(U2-CLK)") (class "Default")
      (node (ref "C3") (pin "1") (pinfunction "1_1") (pintype "bidirectional"))
      (node (ref "R19") (pin "2") (pinfunction "2_2") (pintype "passive"))
      (node (ref "U2") (pin "8") (pinfunction "CLK_8") (pintype "bidirectional"))
    )
    (net (code "35") (name "Net-(U2-GND)") (class "Default")
      (node (ref "C11") (pin "1") (pinfunction "1_1") (pintype "bidirectional"))
      (node (ref "U2") (pin "6") (pinfunction "GND_6") (pintype "bidirectional"))
    )
    (net (code "36") (name "Net-(U2-IN)") (class "Default")
      (node (ref "C7") (pin "1") (pinfunction "1_1") (pintype "bidirectional"))
      (node (ref "U2") (pin "5") (pinfunction "IN_5") (pintype "bidirectional"))
    )
    (net (code "37") (name "Net-(U3-CLK)") (class "Default")
      (node (ref "C4") (pin "1") (pinfunction "1_1") (pintype "bidirectional"))
      (node (ref "R20") (pin "2") (pinfunction "2_2") (pintype "passive"))
      (node (ref "U3") (pin "8") (pinfunction "CLK_8") (pintype "bidirectional"))
    )
    (net (code "38") (name "Net-(U3-GND)") (class "Default")
      (node (ref "C13") (pin "1") (pinfunction "1_1") (pintype "bidirectional"))
      (node (ref "U3") (pin "6") (pinfunction "GND_6") (pintype "bidirectional"))
    )
    (net (code "39") (name "Net-(U3-IN)") (class "Default")
      (node (ref "C8") (pin "1") (pinfunction "1_1") (pintype "bidirectional"))
      (node (ref "U3") (pin "5") (pinfunction "IN_5") (pintype "bidirectional"))
    )
    (net (code "40") (name "Net-(U5-+IN)") (class "Default")
      (node (ref "C21") (pin "2") (pinfunction "2_2") (pintype "bidirectional"))
      (node (ref "R10") (pin "2") (pinfunction "2_2") (pintype "passive"))
      (node (ref "R11") (pin "1") (pinfunction "1_1") (pintype "passive"))
      (node (ref "U5") (pin "3") (pinfunction "+IN_3") (pintype "input"))
    )
    (net (code "41") (name "Net-(U6-+IN)") (class "Default")
      (node (ref "C22") (pin "2") (pinfunction "2_2") (pintype "bidirectional"))
      (node (ref "R12") (pin "2") (pinfunction "2_2") (pintype "passive"))
      (node (ref "R13") (pin "1") (pinfunction "1_1") (pintype "passive"))
      (node (ref "U6") (pin "3") (pinfunction "+IN_3") (pintype "input"))
    )
    (net (code "42") (name "Net-(U7-FB)") (class "Default")
      (node (ref "R21") (pin "2") (pinfunction "2_2") (pintype "passive"))
      (node (ref "R22") (pin "1") (pinfunction "1_1") (pintype "passive"))
      (node (ref "U7") (pin "5") (pinfunction "FB_5") (pintype "bidirectional"))
    )
    (net (code "43") (name "Net-(U7-PG)") (class "Default")
      (node (ref "R18") (pin "1") (pinfunction "1_1") (pintype "passive"))
      (node (ref "U7") (pin "4") (pinfunction "PG_4") (pintype "bidirectional"))
    )
    (net (code "44") (name "Net-(U7-SS{slash}TR)") (class "Default")
      (node (ref "C10") (pin "2") (pinfunction "2_2") (pintype "bidirectional"))
      (node (ref "U7") (pin "9") (pinfunction "SS/TR_9") (pintype "bidirectional"))
    )
    (net (code "45") (name "Net-(U8-OUT)") (class "Default")
      (node (ref "C25") (pin "2") (pinfunction "2_2") (pintype "bidirectional"))
      (node (ref "U8") (pin "1") (pinfunction "OUT_1") (pintype "bidirectional"))
    )
    (net (code "46") (name "PPS") (class "Default")
      (node (ref "J1") (pin "7") (pinfunction "PPS_7") (pintype "bidirectional"))
      (node (ref "TP16") (pin "TESTPOINT") (pinfunction "TESTPOINT_TESTPOINT") (pintype "bidirectional"))
      (node (ref "U1") (pin "37") (pinfunction "PA18_37") (pintype "bidirectional"))
    )
    (net (code "47") (name "SCL") (class "Default")
      (node (ref "J1") (pin "5") (pinfunction "SCL_5") (pintype "bidirectional"))
      (node (ref "TP12") (pin "TESTPOINT") (pinfunction "TESTPOINT_TESTPOINT") (pintype "bidirectional"))
      (node (ref "U1") (pin "44") (pinfunction "PA24_44") (pintype "bidirectional"))
    )
    (net (code "48") (name "SDA") (class "Default")
      (node (ref "J1") (pin "6") (pinfunction "SDA_6") (pintype "bidirectional"))
      (node (ref "TP13") (pin "TESTPOINT") (pinfunction "TESTPOINT_TESTPOINT") (pintype "bidirectional"))
      (node (ref "U1") (pin "43") (pinfunction "PA23_43") (pintype "bidirectional"))
    )
    (net (code "49") (name "SPEC2_GATED") (class "Default")
      (node (ref "C12") (pin "1") (pinfunction "1_1") (pintype "bidirectional"))
      (node (ref "Q1") (pin "3") (pinfunction "D_3") (pintype "passive"))
      (node (ref "R12") (pin "1") (pinfunction "1_1") (pintype "passive"))
      (node (ref "R19") (pin "1") (pinfunction "1_1") (pintype "passive"))
      (node (ref "U2") (pin "1") (pinfunction "VDD_1") (pintype "bidirectional"))
      (node (ref "U6") (pin "5") (pinfunction "V+_5") (pintype "power_in"))
    )
    (net (code "50") (name "SPEC2_OUT") (class "Default")
      (node (ref "TP2") (pin "TESTPOINT") (pinfunction "TESTPOINT_TESTPOINT") (pintype "bidirectional"))
      (node (ref "U1") (pin "12") (pinfunction "PA05_12") (pintype "bidirectional"))
      (node (ref "U2") (pin "3") (pinfunction "OUT_3") (pintype "bidirectional"))
    )
    (net (code "51") (name "SPEC2_POWER") (class "Default")
      (node (ref "Q1") (pin "1") (pinfunction "G_1") (pintype "passive"))
      (node (ref "R23") (pin "1") (pinfunction "1_1") (pintype "passive"))
      (node (ref "TP4") (pin "TESTPOINT") (pinfunction "TESTPOINT_TESTPOINT") (pintype "bidirectional"))
      (node (ref "U1") (pin "20") (pinfunction "PA08_20") (pintype "bidirectional"))
    )
    (net (code "52") (name "SPEC2_RESET") (class "Default")
      (node (ref "TP3") (pin "TESTPOINT") (pinfunction "TESTPOINT_TESTPOINT") (pintype "bidirectional"))
      (node (ref "U1") (pin "16") (pinfunction "PA07_16") (pintype "bidirectional"))
      (node (ref "U2") (pin "7") (pinfunction "RESET_7") (pintype "bidirectional"))
    )
    (net (code "53") (name "SPEC2_STROBE") (class "Default")
      (node (ref "TP5") (pin "TESTPOINT") (pinfunction "TESTPOINT_TESTPOINT") (pintype "bidirectional"))
      (node (ref "U1") (pin "21") (pinfunction "PA09_21") (pintype "bidirectional"))
      (node (ref "U2") (pin "4") (pinfunction "STROBE_4") (pintype "bidirectional"))
    )
    (net (code "54") (name "SPEC_GATED") (class "Default")
      (node (ref "C14") (pin "1") (pinfunction "1_1") (pintype "bidirectional"))
      (node (ref "C23") (pin "2") (pinfunction "2_2") (pintype "bidirectional"))
      (node (ref "C9") (pin "2") (pinfunction "2_2") (pintype "bidirectional"))
      (node (ref "Q2") (pin "3") (pinfunction "D_3") (pintype "passive"))
      (node (ref "R10") (pin "1") (pinfunction "1_1") (pintype "passive"))
      (node (ref "R20") (pin "1") (pinfunction "1_1") (pintype "passive"))
      (node (ref "U3") (pin "1") (pinfunction "VDD_1") (pintype "bidirectional"))
      (node (ref "U5") (pin "5") (pinfunction "V+_5") (pintype "power_in"))
      (node (ref "U8") (pin "2") (pinfunction "VDD_2") (pintype "bidirectional"))
    )
    (net (code "55") (name "SPEC_OUT") (class "Default")
      (node (ref "TP1") (pin "TESTPOINT") (pinfunction "TESTPOINT_TESTPOINT") (pintype "bidirectional"))
      (node (ref "U1") (pin "11") (pinfunction "PA04_11") (pintype "bidirectional"))
      (node (ref "U3") (pin "3") (pinfunction "OUT_3") (pintype "bidirectional"))
    )
    (net (code "56") (name "SPEC_POWER") (class "Default")
      (node (ref "Q2") (pin "1") (pinfunction "G_1") (pintype "passive"))
      (node (ref "R24") (pin "1") (pinfunction "1_1") (pintype "passive"))
      (node (ref "TP8") (pin "TESTPOINT") (pinfunction "TESTPOINT_TESTPOINT") (pintype "bidirectional"))
      (node (ref "U1") (pin "24") (pinfunction "PA12_24") (pintype "bidirectional"))
    )
    (net (code "57") (name "SPEC_RESET") (class "Default")
      (node (ref "TP7") (pin "TESTPOINT") (pinfunction "TESTPOINT_TESTPOINT") (pintype "bidirectional"))
      (node (ref "U1") (pin "23") (pinfunction "PA11_23") (pintype "bidirectional"))
      (node (ref "U3") (pin "7") (pinfunction "RESET_7") (pintype "bidirectional"))
    )
    (net (code "58") (name "SPEC_STROBE") (class "Default")
      (node (ref "TP6") (pin "TESTPOINT") (pinfunction "TESTPOINT_TESTPOINT") (pintype "bidirectional"))
      (node (ref "U1") (pin "22") (pinfunction "PA10_22") (pintype "bidirectional"))
      (node (ref "U3") (pin "4") (pinfunction "STROBE_4") (pintype "bidirectional"))
    )
    (net (code "59") (name "USB+") (class "Default")
      (node (ref "J1") (pin "11") (pinfunction "USB_D+_11") (pintype "bidirectional"))
      (node (ref "U1") (pin "47") (pinfunction "PA26_47") (pintype "bidirectional"))
    )
    (net (code "60") (name "USB-") (class "Default")
      (node (ref "J1") (pin "12") (pinfunction "USB_D-_12") (pintype "bidirectional"))
      (node (ref "U1") (pin "46") (pinfunction "PA25_46") (pintype "bidirectional"))
    )
    (net (code "61") (name "unconnected-(J1-USB_VBUS-Pad13)") (class "Default")
      (node (ref "J1") (pin "13") (pinfunction "USB_VBUS_13") (pintype "bidirectional"))
    )
    (net (code "62") (name "unconnected-(J2-LDET-Pad3)") (class "Default")
      (node (ref "J2") (pin "3") (pinfunction "LDET_3") (pintype "bidirectional"))
    )
    (net (code "63") (name "unconnected-(J2-RDET-Pad2)") (class "Default")
      (node (ref "J2") (pin "2") (pinfunction "RDET_2") (pintype "bidirectional"))
    )
    (net (code "64") (name "unconnected-(J7-SWO-Pad6)") (class "Default")
      (node (ref "J7") (pin "6") (pinfunction "SWO_6") (pintype "bidirectional"))
    )
    (net (code "65") (name "unconnected-(P1-CCW-Pad1)") (class "Default")
      (node (ref "P1") (pin "1") (pinfunction "CCW_1") (pintype "bidirectional"))
    )
    (net (code "66") (name "unconnected-(P2-CCW-Pad1)") (class "Default")
      (node (ref "P2") (pin "1") (pinfunction "CCW_1") (pintype "bidirectional"))
    )
    (net (code "67") (name "unconnected-(U1-ADVREFP-Pad18)") (class "Default")
      (node (ref "U1") (pin "18") (pinfunction "ADVREFP_18") (pintype "bidirectional"))
    )
    (net (code "68") (name "unconnected-(U1-PA06-Pad15)") (class "Default")
      (node (ref "U1") (pin "15") (pinfunction "PA06_15") (pintype "bidirectional"))
    )
    (net (code "69") (name "unconnected-(U1-PA13-Pad32)") (class "Default")
      (node (ref "U1") (pin "32") (pinfunction "PA13_32") (pintype "bidirectional"))
    )
    (net (code "70") (name "unconnected-(U1-PA21-Pad41)") (class "Default")
      (node (ref "U1") (pin "41") (pinfunction "PA21_41") (pintype "bidirectional"))
    )
    (net (code "71") (name "unconnected-(U1-PA22-Pad42)") (class "Default")
      (node (ref "U1") (pin "42") (pinfunction "PA22_42") (pintype "bidirectional"))
    )
    (net (code "72") (name "unconnected-(U1-XIN32-Pad13)") (class "Default")
      (node (ref "U1") (pin "13") (pinfunction "XIN32_13") (pintype "bidirectional"))
    )
    (net (code "73") (name "unconnected-(U1-XOUT32-Pad14)") (class "Default")
      (node (ref "U1") (pin "14") (pinfunction "XOUT32_14") (pintype "bidirectional"))
    )
    (net (code "74") (name "~{CONTROLLER_RESET}") (class "Default")
      (node (ref "J7") (pin "3") (pinfunction "~{RESET}_3") (pintype "bidirectional"))
      (node (ref "S1") (pin "2") (pinfunction "P$2_2") (pintype "passive"))
      (node (ref "U1") (pin "4") (pinfunction "~{RESET}_4") (pintype "bidirectional"))
    )
  )
)
